# accy_feather.net
KiCad netlist of a schematic drawn in EAGLE
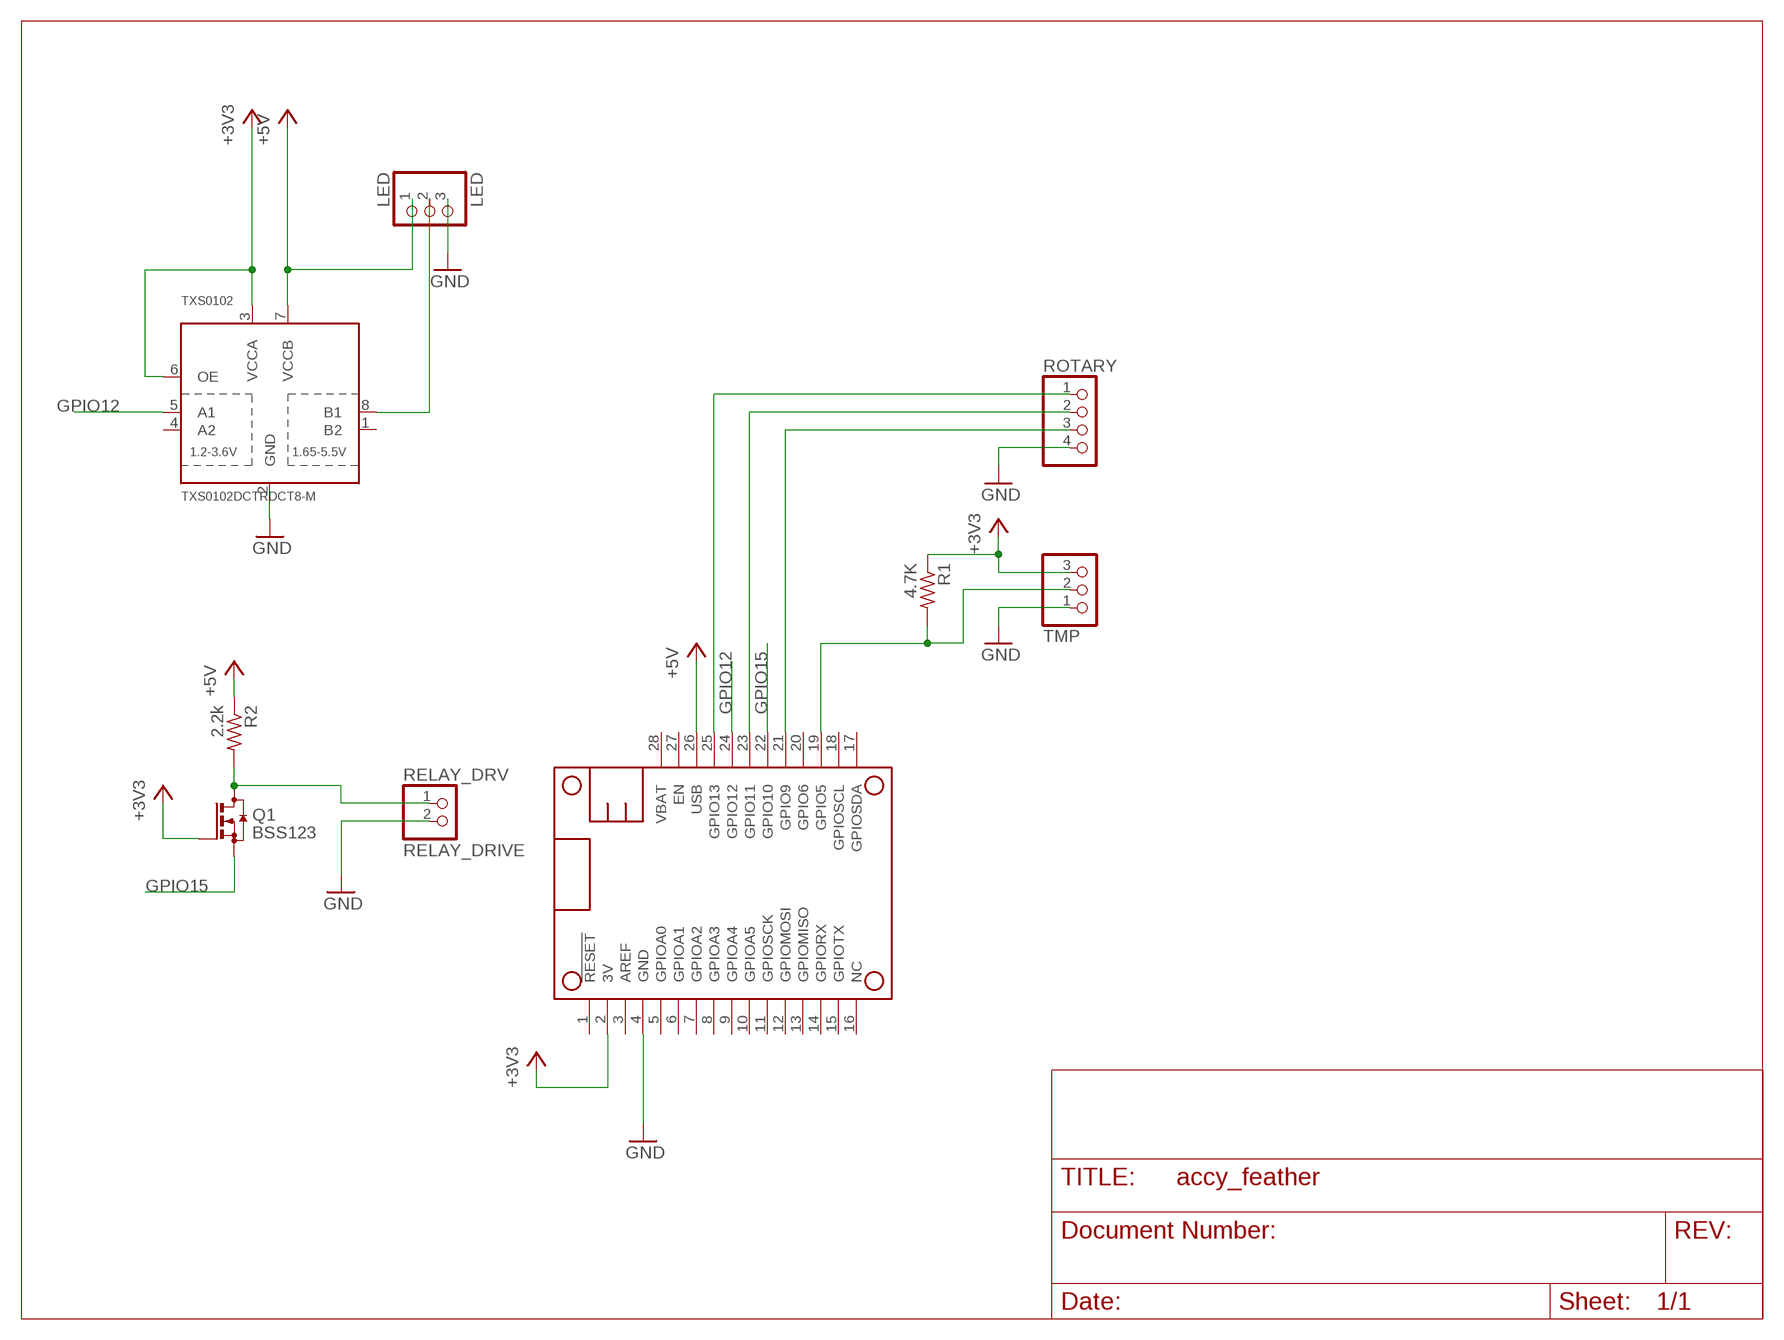
[diagram p0: schematic, sheet 1]

(export (version "E")
  (design (tool "Eeschema 10.0.6"))
  (components
    (comp (ref "LED")
      (value "LED")
      (footprint "eagle-import:1X03-CLEANBIG")
      (libsource (lib "eagle-import") (part "PINHD-1X3CB"))
    )
    (comp (ref "MS1")
      (value "FEATHERWING")
      (footprint "eagle-import:FEATHERWING")
      (libsource (lib "eagle-import") (part "FEATHERWING"))
    )
    (comp (ref "Q1")
      (value "BSS123")
      (footprint "eagle-import:SOT23")
      (libsource (lib "eagle-import") (part "BSS123"))
    )
    (comp (ref "R1")
      (value "4.7K")
      (footprint "eagle-import:R0603")
      (libsource (lib "eagle-import") (part "R-US_R0603"))
    )
    (comp (ref "R2")
      (value "2.2k")
      (footprint "eagle-import:R0603")
      (libsource (lib "eagle-import") (part "R-US_R0603"))
    )
    (comp (ref "RELAY_DRV")
      (value "RELAY_DRIVE")
      (footprint "eagle-import:1X02")
      (libsource (lib "eagle-import") (part "PINHD-1X2"))
    )
    (comp (ref "ROTARY")
      (value "PINHD-1X4")
      (footprint "eagle-import:1X04")
      (libsource (lib "eagle-import") (part "PINHD-1X4"))
    )
    (comp (ref "TMP")
      (value "PINHD-1X3CB")
      (footprint "eagle-import:1X03-CLEANBIG")
      (libsource (lib "eagle-import") (part "PINHD-1X3CB"))
    )
    (comp (ref "TXS0102")
      (value "TXS0102DCTRDCT8-M")
      (footprint "eagle-import:DCT8-M")
      (fields
        (field (name "GENERIC_PART_NUMBER") "TXS0102")
        (field (name "MANUFACTURER") "Texas Instruments")
        (field (name "MANUFACTURER_PART_NUMBER") "TXS0102DCTR")
        (field (name "COPYRIGHT") "Copyright C 2015 Accelerated Designs. All rights reserved")
      )
      (libsource (lib "eagle-import") (part "TXS0102DCTRDCT8-M"))
    )
  )
  (nets
    (net (code "1") (name "+3V3") (class "Default")
      (node (ref "MS1") (pin "2") (pinfunction "3V_2") (pintype "power_in"))
      (node (ref "Q1") (pin "1") (pinfunction "G_1") (pintype "passive"))
      (node (ref "R1") (pin "1") (pinfunction "1_1") (pintype "passive"))
      (node (ref "TMP") (pin "3") (pinfunction "3_3") (pintype "passive"))
      (node (ref "TXS0102") (pin "3") (pinfunction "VCCA_3") (pintype "bidirectional"))
      (node (ref "TXS0102") (pin "6") (pinfunction "OE_6") (pintype "bidirectional"))
    )
    (net (code "2") (name "+5V") (class "Default")
      (node (ref "LED") (pin "1") (pinfunction "1_1") (pintype "passive"))
      (node (ref "MS1") (pin "26") (pinfunction "USB_26") (pintype "power_in"))
      (node (ref "R2") (pin "1") (pinfunction "1_1") (pintype "passive"))
      (node (ref "TXS0102") (pin "7") (pinfunction "VCCB_7") (pintype "bidirectional"))
    )
    (net (code "3") (name "/GPIO12") (class "Default")
      (node (ref "MS1") (pin "24") (pinfunction "GPIO12_24") (pintype "bidirectional"))
      (node (ref "TXS0102") (pin "5") (pinfunction "A1_5") (pintype "bidirectional"))
    )
    (net (code "4") (name "/GPIO15") (class "Default")
      (node (ref "MS1") (pin "22") (pinfunction "GPIO10_22") (pintype "bidirectional"))
      (node (ref "Q1") (pin "2") (pinfunction "S_2") (pintype "passive"))
    )
    (net (code "5") (name "/VBAT") (class "Default")
      (node (ref "MS1") (pin "28") (pinfunction "VBAT_28") (pintype "power_in"))
    )
    (net (code "6") (name "GND") (class "Default")
      (node (ref "LED") (pin "3") (pinfunction "3_3") (pintype "passive"))
      (node (ref "MS1") (pin "4") (pinfunction "GND_4") (pintype "power_in"))
      (node (ref "RELAY_DRV") (pin "2") (pinfunction "2_2") (pintype "passive"))
      (node (ref "ROTARY") (pin "4") (pinfunction "4_4") (pintype "passive"))
      (node (ref "TMP") (pin "1") (pinfunction "1_1") (pintype "passive"))
      (node (ref "TXS0102") (pin "2") (pinfunction "GND_2") (pintype "bidirectional"))
    )
    (net (code "7") (name "Net-(MS1-GPIO5)") (class "Default")
      (node (ref "MS1") (pin "19") (pinfunction "GPIO5_19") (pintype "bidirectional"))
      (node (ref "R1") (pin "2") (pinfunction "2_2") (pintype "passive"))
      (node (ref "TMP") (pin "2") (pinfunction "2_2") (pintype "passive"))
    )
    (net (code "8") (name "Net-(MS1-GPIO9)") (class "Default")
      (node (ref "MS1") (pin "21") (pinfunction "GPIO9_21") (pintype "bidirectional"))
      (node (ref "ROTARY") (pin "3") (pinfunction "3_3") (pintype "passive"))
    )
    (net (code "9") (name "Net-(MS1-GPIO11)") (class "Default")
      (node (ref "MS1") (pin "23") (pinfunction "GPIO11_23") (pintype "bidirectional"))
      (node (ref "ROTARY") (pin "2") (pinfunction "2_2") (pintype "passive"))
    )
    (net (code "10") (name "Net-(MS1-GPIO13)") (class "Default")
      (node (ref "MS1") (pin "25") (pinfunction "GPIO13_25") (pintype "bidirectional"))
      (node (ref "ROTARY") (pin "1") (pinfunction "1_1") (pintype "passive"))
    )
    (net (code "11") (name "Net-(Q1-D)") (class "Default")
      (node (ref "Q1") (pin "3") (pinfunction "D_3") (pintype "passive"))
      (node (ref "R2") (pin "2") (pinfunction "2_2") (pintype "passive"))
      (node (ref "RELAY_DRV") (pin "1") (pinfunction "1_1") (pintype "passive"))
    )
    (net (code "12") (name "Net-(TXS0102-B1)") (class "Default")
      (node (ref "LED") (pin "2") (pinfunction "2_2") (pintype "passive"))
      (node (ref "TXS0102") (pin "8") (pinfunction "B1_8") (pintype "bidirectional"))
    )
    (net (code "13") (name "unconnected-(MS1-AREF-Pad3)") (class "Default")
      (node (ref "MS1") (pin "3") (pinfunction "AREF_3") (pintype "passive"))
    )
    (net (code "14") (name "unconnected-(MS1-EN-Pad27)") (class "Default")
      (node (ref "MS1") (pin "27") (pinfunction "EN_27") (pintype "passive"))
    )
    (net (code "15") (name "unconnected-(MS1-GPIO6-Pad20)") (class "Default")
      (node (ref "MS1") (pin "20") (pinfunction "GPIO6_20") (pintype "bidirectional"))
    )
    (net (code "16") (name "unconnected-(MS1-GPIOA0-Pad5)") (class "Default")
      (node (ref "MS1") (pin "5") (pinfunction "GPIOA0_5") (pintype "bidirectional"))
    )
    (net (code "17") (name "unconnected-(MS1-GPIOA1-Pad6)") (class "Default")
      (node (ref "MS1") (pin "6") (pinfunction "GPIOA1_6") (pintype "bidirectional"))
    )
    (net (code "18") (name "unconnected-(MS1-GPIOA2-Pad7)") (class "Default")
      (node (ref "MS1") (pin "7") (pinfunction "GPIOA2_7") (pintype "bidirectional"))
    )
    (net (code "19") (name "unconnected-(MS1-GPIOA3-Pad8)") (class "Default")
      (node (ref "MS1") (pin "8") (pinfunction "GPIOA3_8") (pintype "bidirectional"))
    )
    (net (code "20") (name "unconnected-(MS1-GPIOA4-Pad9)") (class "Default")
      (node (ref "MS1") (pin "9") (pinfunction "GPIOA4_9") (pintype "bidirectional"))
    )
    (net (code "21") (name "unconnected-(MS1-GPIOA5-Pad10)") (class "Default")
      (node (ref "MS1") (pin "10") (pinfunction "GPIOA5_10") (pintype "bidirectional"))
    )
    (net (code "22") (name "unconnected-(MS1-GPIOMISO-Pad13)") (class "Default")
      (node (ref "MS1") (pin "13") (pinfunction "GPIOMISO_13") (pintype "bidirectional"))
    )
    (net (code "23") (name "unconnected-(MS1-GPIOMOSI-Pad12)") (class "Default")
      (node (ref "MS1") (pin "12") (pinfunction "GPIOMOSI_12") (pintype "bidirectional"))
    )
    (net (code "24") (name "unconnected-(MS1-GPIORX-Pad14)") (class "Default")
      (node (ref "MS1") (pin "14") (pinfunction "GPIORX_14") (pintype "bidirectional"))
    )
    (net (code "25") (name "unconnected-(MS1-GPIOSCK-Pad11)") (class "Default")
      (node (ref "MS1") (pin "11") (pinfunction "GPIOSCK_11") (pintype "bidirectional"))
    )
    (net (code "26") (name "unconnected-(MS1-GPIOSCL-Pad18)") (class "Default")
      (node (ref "MS1") (pin "18") (pinfunction "GPIOSCL_18") (pintype "bidirectional"))
    )
    (net (code "27") (name "unconnected-(MS1-GPIOSDA-Pad17)") (class "Default")
      (node (ref "MS1") (pin "17") (pinfunction "GPIOSDA_17") (pintype "bidirectional"))
    )
    (net (code "28") (name "unconnected-(MS1-GPIOTX-Pad15)") (class "Default")
      (node (ref "MS1") (pin "15") (pinfunction "GPIOTX_15") (pintype "bidirectional"))
    )
    (net (code "29") (name "unconnected-(MS1-NC-Pad16)") (class "Default")
      (node (ref "MS1") (pin "16") (pinfunction "NC_16") (pintype "passive"))
    )
    (net (code "30") (name "unconnected-(MS1-~{RESET}-Pad1)") (class "Default")
      (node (ref "MS1") (pin "1") (pinfunction "~{RESET}_1") (pintype "input"))
    )
    (net (code "31") (name "unconnected-(TXS0102-A2-Pad4)") (class "Default")
      (node (ref "TXS0102") (pin "4") (pinfunction "A2_4") (pintype "bidirectional"))
    )
    (net (code "32") (name "unconnected-(TXS0102-B2-Pad1)") (class "Default")
      (node (ref "TXS0102") (pin "1") (pinfunction "B2_1") (pintype "bidirectional"))
    )
  )
)
